# Yaesu_to_CIV_FET.net
KiCad netlist of a schematic drawn in EAGLE
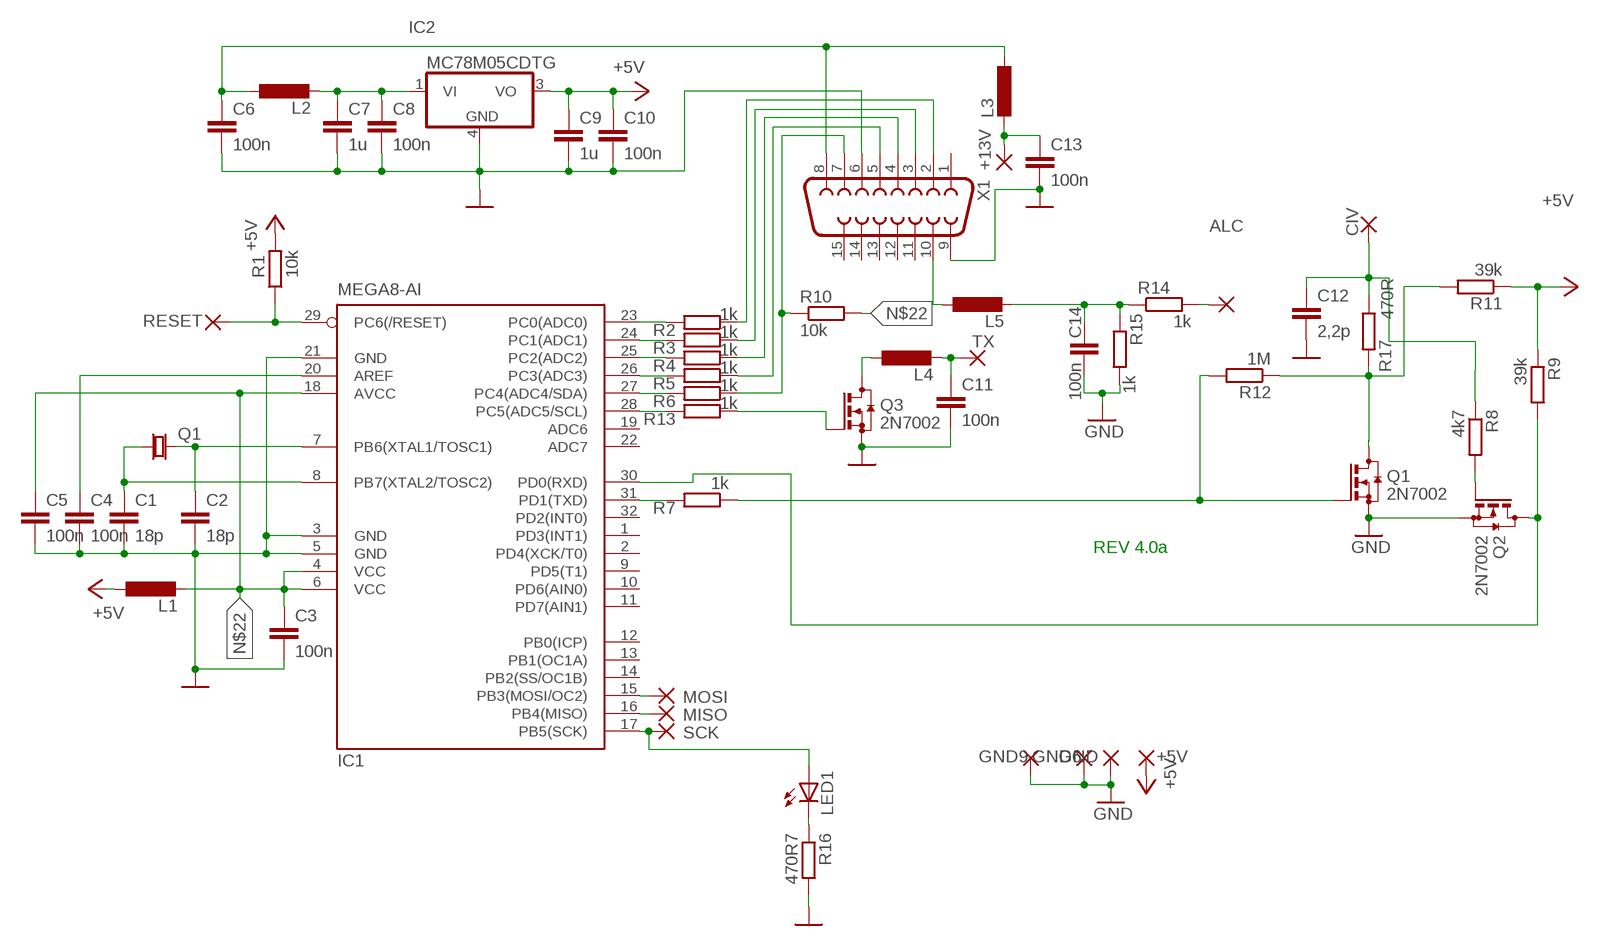
[diagram p0: schematic, sheet 1]

(export (version "E")
  (design (tool "Eeschema 10.0.6"))
  (components
    (comp (ref "+5V")
      (value "SMD2")
      (footprint "eagle-import:SMD1,27-2,54")
      (libsource (lib "eagle-import") (part "SMD2"))
    )
    (comp (ref "+13V")
      (value "SMD2")
      (footprint "eagle-import:SMD1,27-2,54")
      (libsource (lib "eagle-import") (part "SMD2"))
    )
    (comp (ref "ALC")
      (value "SMD2")
      (footprint "eagle-import:SMD1,27-2,54")
      (libsource (lib "eagle-import") (part "SMD2"))
    )
    (comp (ref "C1")
      (value "18p")
      (footprint "eagle-import:C0603K")
      (libsource (lib "eagle-import") (part "C-EUC0603K"))
    )
    (comp (ref "C2")
      (value "18p")
      (footprint "eagle-import:C0603K")
      (libsource (lib "eagle-import") (part "C-EUC0603K"))
    )
    (comp (ref "C3")
      (value "100n")
      (footprint "eagle-import:C0603K")
      (libsource (lib "eagle-import") (part "C-EUC0603K"))
    )
    (comp (ref "C4")
      (value "100n")
      (footprint "eagle-import:C0603K")
      (libsource (lib "eagle-import") (part "C-EUC0603K"))
    )
    (comp (ref "C5")
      (value "100n")
      (footprint "eagle-import:C0603K")
      (libsource (lib "eagle-import") (part "C-EUC0603K"))
    )
    (comp (ref "C6")
      (value "100n")
      (footprint "eagle-import:C0603K")
      (libsource (lib "eagle-import") (part "C-EUC0603K"))
    )
    (comp (ref "C7")
      (value "1u")
      (footprint "eagle-import:C0805K")
      (libsource (lib "eagle-import") (part "C-EUC0805K"))
    )
    (comp (ref "C8")
      (value "100n")
      (footprint "eagle-import:C0603K")
      (libsource (lib "eagle-import") (part "C-EUC0603K"))
    )
    (comp (ref "C9")
      (value "1u")
      (footprint "eagle-import:C0805K")
      (libsource (lib "eagle-import") (part "C-EUC0805K"))
    )
    (comp (ref "C10")
      (value "100n")
      (footprint "eagle-import:C0603K")
      (libsource (lib "eagle-import") (part "C-EUC0603K"))
    )
    (comp (ref "C11")
      (value "100n")
      (footprint "eagle-import:C0603K")
      (libsource (lib "eagle-import") (part "C-EUC0603K"))
    )
    (comp (ref "C12")
      (value "2,2p")
      (footprint "eagle-import:C0603K")
      (libsource (lib "eagle-import") (part "C-EUC0603K"))
    )
    (comp (ref "C13")
      (value "100n")
      (footprint "eagle-import:C0603K")
      (libsource (lib "eagle-import") (part "C-EUC0603K"))
    )
    (comp (ref "C14")
      (value "100n")
      (footprint "eagle-import:C0603K")
      (libsource (lib "eagle-import") (part "C-EUC0603K"))
    )
    (comp (ref "CIV")
      (value "SMD2")
      (footprint "eagle-import:SMD1,27-2,54")
      (libsource (lib "eagle-import") (part "SMD2"))
    )
    (comp (ref "GND")
      (value "SMD2")
      (footprint "eagle-import:SMD1,27-2,54")
      (libsource (lib "eagle-import") (part "SMD2"))
    )
    (comp (ref "GND6")
      (value "SMD2")
      (footprint "eagle-import:SMD1,27-2,54")
      (libsource (lib "eagle-import") (part "SMD2"))
    )
    (comp (ref "GND9")
      (value "SMD2")
      (footprint "eagle-import:SMD1,27-2,54")
      (libsource (lib "eagle-import") (part "SMD2"))
    )
    (comp (ref "IC1")
      (value "MEGA8-AI")
      (footprint "eagle-import:TQFP32-08")
      (fields (field (name "MPN") "ATMEGA8-16AU"))
      (libsource (lib "eagle-import") (part "MEGA8-AI"))
    )
    (comp (ref "IC2")
      (value "MC78M05CDTG")
      (footprint "eagle-import:DPACK_3")
      (libsource (lib "eagle-import") (part "MC78M05CDTG"))
    )
    (comp (ref "L1")
      (value "L-EUL2012C")
      (footprint "eagle-import:L2012C")
      (libsource (lib "eagle-import") (part "L-EUL2012C"))
    )
    (comp (ref "L2")
      (value "L-EUL1812")
      (footprint "eagle-import:L1812")
      (libsource (lib "eagle-import") (part "L-EUL1812"))
    )
    (comp (ref "L3")
      (value "L-EUL1812")
      (footprint "eagle-import:L1812")
      (libsource (lib "eagle-import") (part "L-EUL1812"))
    )
    (comp (ref "L4")
      (value "L-EUL2012C")
      (footprint "eagle-import:L2012C")
      (libsource (lib "eagle-import") (part "L-EUL2012C"))
    )
    (comp (ref "L5")
      (value "L-EUL2012C")
      (footprint "eagle-import:L2012C")
      (libsource (lib "eagle-import") (part "L-EUL2012C"))
    )
    (comp (ref "LED1")
      (value "LEDCHIP-LED0603")
      (footprint "eagle-import:CHIP-LED0603")
      (libsource (lib "eagle-import") (part "LEDCHIP-LED0603"))
    )
    (comp (ref "MISO")
      (value "SMD2")
      (footprint "eagle-import:SMD1,27-2,54")
      (libsource (lib "eagle-import") (part "SMD2"))
    )
    (comp (ref "MOSI")
      (value "SMD2")
      (footprint "eagle-import:SMD1,27-2,54")
      (libsource (lib "eagle-import") (part "SMD2"))
    )
    (comp (ref "Q1")
      (value "2N7002")
      (footprint "eagle-import:SOT23")
      (libsource (lib "eagle-import") (part "BSS123"))
    )
    (comp (ref "Q2")
      (value "2N7002")
      (footprint "eagle-import:SOT23")
      (libsource (lib "eagle-import") (part "BSS123"))
    )
    (comp (ref "Q3")
      (value "2N7002")
      (footprint "eagle-import:SOT23")
      (libsource (lib "eagle-import") (part "BSS123"))
    )
    (comp (ref "R1")
      (value "10k")
      (footprint "eagle-import:R0603")
      (libsource (lib "eagle-import") (part "R-EU_R0603"))
    )
    (comp (ref "R2")
      (value "1k")
      (footprint "eagle-import:R0603")
      (libsource (lib "eagle-import") (part "R-EU_R0603"))
    )
    (comp (ref "R3")
      (value "1k")
      (footprint "eagle-import:R0603")
      (libsource (lib "eagle-import") (part "R-EU_R0603"))
    )
    (comp (ref "R4")
      (value "1k")
      (footprint "eagle-import:R0603")
      (libsource (lib "eagle-import") (part "R-EU_R0603"))
    )
    (comp (ref "R5")
      (value "1k")
      (footprint "eagle-import:R0603")
      (libsource (lib "eagle-import") (part "R-EU_R0603"))
    )
    (comp (ref "R6")
      (value "1k")
      (footprint "eagle-import:R0603")
      (libsource (lib "eagle-import") (part "R-EU_R0603"))
    )
    (comp (ref "R7")
      (value "1k")
      (footprint "eagle-import:R0603")
      (libsource (lib "eagle-import") (part "R-EU_R0603"))
    )
    (comp (ref "R8")
      (value "4k7")
      (footprint "eagle-import:R0603")
      (libsource (lib "eagle-import") (part "R-EU_R0603"))
    )
    (comp (ref "R9")
      (value "39k")
      (footprint "eagle-import:R0603")
      (libsource (lib "eagle-import") (part "R-EU_R0603"))
    )
    (comp (ref "R10")
      (value "10k")
      (footprint "eagle-import:R0603")
      (libsource (lib "eagle-import") (part "R-EU_R0603"))
    )
    (comp (ref "R11")
      (value "39k")
      (footprint "eagle-import:R0603")
      (libsource (lib "eagle-import") (part "R-EU_R0603"))
    )
    (comp (ref "R12")
      (value "1M")
      (footprint "eagle-import:R0603")
      (libsource (lib "eagle-import") (part "R-EU_R0603"))
    )
    (comp (ref "R13")
      (value "1k")
      (footprint "eagle-import:R0603")
      (libsource (lib "eagle-import") (part "R-EU_R0603"))
    )
    (comp (ref "R14")
      (value "1k")
      (footprint "eagle-import:R0603")
      (libsource (lib "eagle-import") (part "R-EU_R0603"))
    )
    (comp (ref "R15")
      (value "1k")
      (footprint "eagle-import:R0603")
      (libsource (lib "eagle-import") (part "R-EU_R0603"))
    )
    (comp (ref "R16")
      (value "470R7")
      (footprint "eagle-import:R0603")
      (libsource (lib "eagle-import") (part "R-EU_R0603"))
    )
    (comp (ref "R17")
      (value "470R")
      (footprint "eagle-import:R0603")
      (libsource (lib "eagle-import") (part "R-EU_R0603"))
    )
    (comp (ref "RESET")
      (value "SMD2")
      (footprint "eagle-import:SMD1,27-2,54")
      (libsource (lib "eagle-import") (part "SMD2"))
    )
    (comp (ref "SCK")
      (value "SMD2")
      (footprint "eagle-import:SMD1,27-2,54")
      (libsource (lib "eagle-import") (part "SMD2"))
    )
    (comp (ref "TX")
      (value "SMD2")
      (footprint "eagle-import:SMD1,27-2,54")
      (libsource (lib "eagle-import") (part "SMD2"))
    )
    (comp (ref "X1")
      (value "F15D")
      (footprint "eagle-import:F15D")
      (libsource (lib "eagle-import") (part "F15D"))
    )
  )
  (nets
    (net (code "1") (name "+5V") (class "Default")
      (node (ref "+5V") (pin "1") (pinfunction "P_1") (pintype "passive"))
      (node (ref "C10") (pin "1") (pinfunction "1_1") (pintype "passive"))
      (node (ref "C9") (pin "1") (pinfunction "1_1") (pintype "passive"))
      (node (ref "IC2") (pin "3") (pinfunction "VO_3") (pintype "passive"))
      (node (ref "L1") (pin "1") (pinfunction "1_1") (pintype "passive"))
      (node (ref "R1") (pin "2") (pinfunction "2_2") (pintype "passive"))
      (node (ref "R11") (pin "1") (pinfunction "1_1") (pintype "passive"))
      (node (ref "R9") (pin "1") (pinfunction "1_1") (pintype "passive"))
    )
    (net (code "2") (name "GND") (class "Default")
      (node (ref "C1") (pin "2") (pinfunction "2_2") (pintype "passive"))
      (node (ref "C10") (pin "2") (pinfunction "2_2") (pintype "passive"))
      (node (ref "C11") (pin "2") (pinfunction "2_2") (pintype "passive"))
      (node (ref "C12") (pin "2") (pinfunction "2_2") (pintype "passive"))
      (node (ref "C13") (pin "2") (pinfunction "2_2") (pintype "passive"))
      (node (ref "C14") (pin "2") (pinfunction "2_2") (pintype "passive"))
      (node (ref "C2") (pin "2") (pinfunction "2_2") (pintype "passive"))
      (node (ref "C3") (pin "2") (pinfunction "2_2") (pintype "passive"))
      (node (ref "C4") (pin "2") (pinfunction "2_2") (pintype "passive"))
      (node (ref "C5") (pin "2") (pinfunction "2_2") (pintype "passive"))
      (node (ref "C6") (pin "2") (pinfunction "2_2") (pintype "passive"))
      (node (ref "C7") (pin "2") (pinfunction "2_2") (pintype "passive"))
      (node (ref "C8") (pin "2") (pinfunction "2_2") (pintype "passive"))
      (node (ref "C9") (pin "2") (pinfunction "2_2") (pintype "passive"))
      (node (ref "GND") (pin "1") (pinfunction "P_1") (pintype "passive"))
      (node (ref "GND6") (pin "1") (pinfunction "P_1") (pintype "passive"))
      (node (ref "GND9") (pin "1") (pinfunction "P_1") (pintype "passive"))
      (node (ref "IC1") (pin "21") (pinfunction "GND_21") (pintype "power_in"))
      (node (ref "IC1") (pin "3") (pinfunction "GND_3") (pintype "power_in"))
      (node (ref "IC1") (pin "5") (pinfunction "GND_5") (pintype "power_in"))
      (node (ref "IC2") (pin "4") (pinfunction "GND_4") (pintype "passive"))
      (node (ref "Q1") (pin "2") (pinfunction "S_2") (pintype "passive"))
      (node (ref "Q2") (pin "2") (pinfunction "S_2") (pintype "passive"))
      (node (ref "Q3") (pin "2") (pinfunction "S_2") (pintype "passive"))
      (node (ref "R15") (pin "2") (pinfunction "2_2") (pintype "passive"))
      (node (ref "R16") (pin "2") (pinfunction "2_2") (pintype "passive"))
      (node (ref "X1") (pin "6") (pinfunction "6_6") (pintype "passive"))
      (node (ref "X1") (pin "9") (pinfunction "9_9") (pintype "passive"))
    )
    (net (code "3") (name "N$22") (class "Default")
      (node (ref "C3") (pin "1") (pinfunction "1_1") (pintype "passive"))
      (node (ref "C5") (pin "1") (pinfunction "1_1") (pintype "passive"))
      (node (ref "IC1") (pin "18") (pinfunction "AVCC_18") (pintype "power_in"))
      (node (ref "IC1") (pin "4") (pinfunction "VCC_4") (pintype "power_in"))
      (node (ref "IC1") (pin "6") (pinfunction "VCC_6") (pintype "power_in"))
      (node (ref "L1") (pin "2") (pinfunction "2_2") (pintype "passive"))
      (node (ref "R10") (pin "2") (pinfunction "2_2") (pintype "passive"))
    )
    (net (code "4") (name "Net-(+13V-P)") (class "Default")
      (node (ref "+13V") (pin "1") (pinfunction "P_1") (pintype "passive"))
      (node (ref "C13") (pin "1") (pinfunction "1_1") (pintype "passive"))
      (node (ref "L3") (pin "2") (pinfunction "2_2") (pintype "passive"))
    )
    (net (code "5") (name "Net-(ALC-P)") (class "Default")
      (node (ref "ALC") (pin "1") (pinfunction "P_1") (pintype "passive"))
      (node (ref "R14") (pin "2") (pinfunction "2_2") (pintype "passive"))
    )
    (net (code "6") (name "Net-(C6-Pad1)") (class "Default")
      (node (ref "C6") (pin "1") (pinfunction "1_1") (pintype "passive"))
      (node (ref "L2") (pin "1") (pinfunction "1_1") (pintype "passive"))
      (node (ref "L3") (pin "1") (pinfunction "1_1") (pintype "passive"))
      (node (ref "X1") (pin "8") (pinfunction "8_8") (pintype "passive"))
    )
    (net (code "7") (name "Net-(C14-Pad1)") (class "Default")
      (node (ref "C14") (pin "1") (pinfunction "1_1") (pintype "passive"))
      (node (ref "L5") (pin "2") (pinfunction "2_2") (pintype "passive"))
      (node (ref "R14") (pin "1") (pinfunction "1_1") (pintype "passive"))
      (node (ref "R15") (pin "1") (pinfunction "1_1") (pintype "passive"))
    )
    (net (code "8") (name "Net-(CIV-P)") (class "Default")
      (node (ref "C12") (pin "1") (pinfunction "1_1") (pintype "passive"))
      (node (ref "CIV") (pin "1") (pinfunction "P_1") (pintype "passive"))
      (node (ref "R17") (pin "1") (pinfunction "1_1") (pintype "passive"))
      (node (ref "R8") (pin "1") (pinfunction "1_1") (pintype "passive"))
    )
    (net (code "9") (name "Net-(IC1-AREF)") (class "Default")
      (node (ref "C4") (pin "1") (pinfunction "1_1") (pintype "passive"))
      (node (ref "IC1") (pin "20") (pinfunction "AREF_20") (pintype "passive"))
    )
    (net (code "10") (name "Net-(IC1-PB3(MOSI{slash}OC2))") (class "Default")
      (node (ref "IC1") (pin "15") (pinfunction "PB3(MOSI/OC2)_15") (pintype "bidirectional"))
      (node (ref "MOSI") (pin "1") (pinfunction "P_1") (pintype "passive"))
    )
    (net (code "11") (name "Net-(IC1-PB4(MISO))") (class "Default")
      (node (ref "IC1") (pin "16") (pinfunction "PB4(MISO)_16") (pintype "bidirectional"))
      (node (ref "MISO") (pin "1") (pinfunction "P_1") (pintype "passive"))
    )
    (net (code "12") (name "Net-(IC1-PB5(SCK))") (class "Default")
      (node (ref "IC1") (pin "17") (pinfunction "PB5(SCK)_17") (pintype "bidirectional"))
      (node (ref "LED1") (pin "A") (pinfunction "A_A") (pintype "passive"))
      (node (ref "SCK") (pin "1") (pinfunction "P_1") (pintype "passive"))
    )
    (net (code "13") (name "Net-(IC1-PB6(XTAL1{slash}TOSC1))") (class "Default")
      (node (ref "C2") (pin "1") (pinfunction "1_1") (pintype "passive"))
      (node (ref "IC1") (pin "7") (pinfunction "PB6(XTAL1/TOSC1)_7") (pintype "bidirectional"))
    )
    (net (code "14") (name "Net-(IC1-PB7(XTAL2{slash}TOSC2))") (class "Default")
      (node (ref "C1") (pin "1") (pinfunction "1_1") (pintype "passive"))
      (node (ref "IC1") (pin "8") (pinfunction "PB7(XTAL2/TOSC2)_8") (pintype "bidirectional"))
    )
    (net (code "15") (name "Net-(IC1-PC0(ADC0))") (class "Default")
      (node (ref "IC1") (pin "23") (pinfunction "PC0(ADC0)_23") (pintype "bidirectional"))
      (node (ref "R2") (pin "2") (pinfunction "2_2") (pintype "passive"))
    )
    (net (code "16") (name "Net-(IC1-PC1(ADC1))") (class "Default")
      (node (ref "IC1") (pin "24") (pinfunction "PC1(ADC1)_24") (pintype "bidirectional"))
      (node (ref "R3") (pin "2") (pinfunction "2_2") (pintype "passive"))
    )
    (net (code "17") (name "Net-(IC1-PC2(ADC2))") (class "Default")
      (node (ref "IC1") (pin "25") (pinfunction "PC2(ADC2)_25") (pintype "bidirectional"))
      (node (ref "R4") (pin "2") (pinfunction "2_2") (pintype "passive"))
    )
    (net (code "18") (name "Net-(IC1-PC3(ADC3))") (class "Default")
      (node (ref "IC1") (pin "26") (pinfunction "PC3(ADC3)_26") (pintype "bidirectional"))
      (node (ref "R5") (pin "2") (pinfunction "2_2") (pintype "passive"))
    )
    (net (code "19") (name "Net-(IC1-PC4(ADC4{slash}SDA))") (class "Default")
      (node (ref "IC1") (pin "27") (pinfunction "PC4(ADC4/SDA)_27") (pintype "bidirectional"))
      (node (ref "R6") (pin "2") (pinfunction "2_2") (pintype "passive"))
    )
    (net (code "20") (name "Net-(IC1-PC5(ADC5{slash}SCL))") (class "Default")
      (node (ref "IC1") (pin "28") (pinfunction "PC5(ADC5/SCL)_28") (pintype "bidirectional"))
      (node (ref "R13") (pin "2") (pinfunction "2_2") (pintype "passive"))
    )
    (net (code "21") (name "Net-(IC1-PC6({slash}RESET))") (class "Default")
      (node (ref "IC1") (pin "29") (pinfunction "PC6(/RESET)_29") (pintype "bidirectional"))
      (node (ref "R1") (pin "1") (pinfunction "1_1") (pintype "passive"))
      (node (ref "RESET") (pin "1") (pinfunction "P_1") (pintype "passive"))
    )
    (net (code "22") (name "Net-(IC1-PD0(RXD))") (class "Default")
      (node (ref "IC1") (pin "30") (pinfunction "PD0(RXD)_30") (pintype "bidirectional"))
      (node (ref "Q2") (pin "3") (pinfunction "D_3") (pintype "passive"))
      (node (ref "R9") (pin "2") (pinfunction "2_2") (pintype "passive"))
    )
    (net (code "23") (name "Net-(IC1-PD1(TXD))") (class "Default")
      (node (ref "IC1") (pin "31") (pinfunction "PD1(TXD)_31") (pintype "bidirectional"))
      (node (ref "R7") (pin "2") (pinfunction "2_2") (pintype "passive"))
    )
    (net (code "24") (name "Net-(IC2-VI)") (class "Default")
      (node (ref "C7") (pin "1") (pinfunction "1_1") (pintype "passive"))
      (node (ref "C8") (pin "1") (pinfunction "1_1") (pintype "passive"))
      (node (ref "IC2") (pin "1") (pinfunction "VI_1") (pintype "input"))
      (node (ref "L2") (pin "2") (pinfunction "2_2") (pintype "passive"))
    )
    (net (code "25") (name "Net-(L5-Pad1)") (class "Default")
      (node (ref "L5") (pin "1") (pinfunction "1_1") (pintype "passive"))
      (node (ref "X1") (pin "10") (pinfunction "10_10") (pintype "passive"))
    )
    (net (code "26") (name "Net-(LED1-PadC)") (class "Default")
      (node (ref "LED1") (pin "C") (pinfunction "C_C") (pintype "passive"))
      (node (ref "R16") (pin "1") (pinfunction "1_1") (pintype "passive"))
    )
    (net (code "27") (name "Net-(Q1-G)") (class "Default")
      (node (ref "Q1") (pin "1") (pinfunction "G_1") (pintype "passive"))
      (node (ref "R12") (pin "2") (pinfunction "2_2") (pintype "passive"))
      (node (ref "R7") (pin "1") (pinfunction "1_1") (pintype "passive"))
    )
    (net (code "28") (name "Net-(Q2-G)") (class "Default")
      (node (ref "Q2") (pin "1") (pinfunction "G_1") (pintype "passive"))
      (node (ref "R8") (pin "2") (pinfunction "2_2") (pintype "passive"))
    )
    (net (code "29") (name "Net-(Q3-D)") (class "Default")
      (node (ref "L4") (pin "1") (pinfunction "1_1") (pintype "passive"))
      (node (ref "Q3") (pin "3") (pinfunction "D_3") (pintype "passive"))
    )
    (net (code "30") (name "Net-(Q3-G)") (class "Default")
      (node (ref "Q3") (pin "1") (pinfunction "G_1") (pintype "passive"))
      (node (ref "R13") (pin "1") (pinfunction "1_1") (pintype "passive"))
    )
    (net (code "31") (name "Net-(R2-Pad1)") (class "Default")
      (node (ref "R2") (pin "1") (pinfunction "1_1") (pintype "passive"))
      (node (ref "X1") (pin "2") (pinfunction "2_2") (pintype "passive"))
    )
    (net (code "32") (name "Net-(R3-Pad1)") (class "Default")
      (node (ref "R3") (pin "1") (pinfunction "1_1") (pintype "passive"))
      (node (ref "X1") (pin "3") (pinfunction "3_3") (pintype "passive"))
    )
    (net (code "33") (name "Net-(R4-Pad1)") (class "Default")
      (node (ref "R4") (pin "1") (pinfunction "1_1") (pintype "passive"))
      (node (ref "X1") (pin "4") (pinfunction "4_4") (pintype "passive"))
    )
    (net (code "34") (name "Net-(R5-Pad1)") (class "Default")
      (node (ref "R5") (pin "1") (pinfunction "1_1") (pintype "passive"))
      (node (ref "X1") (pin "5") (pinfunction "5_5") (pintype "passive"))
    )
    (net (code "35") (name "Net-(R10-Pad1)") (class "Default")
      (node (ref "R10") (pin "1") (pinfunction "1_1") (pintype "passive"))
      (node (ref "R6") (pin "1") (pinfunction "1_1") (pintype "passive"))
      (node (ref "X1") (pin "7") (pinfunction "7_7") (pintype "passive"))
    )
    (net (code "36") (name "Net-(R11-Pad2)") (class "Default")
      (node (ref "R11") (pin "2") (pinfunction "2_2") (pintype "passive"))
      (node (ref "R12") (pin "1") (pinfunction "1_1") (pintype "passive"))
      (node (ref "R17") (pin "2") (pinfunction "2_2") (pintype "passive"))
    )
    (net (code "37") (name "Net-(TX-P)") (class "Default")
      (node (ref "C11") (pin "1") (pinfunction "1_1") (pintype "passive"))
      (node (ref "L4") (pin "2") (pinfunction "2_2") (pintype "passive"))
      (node (ref "TX") (pin "1") (pinfunction "P_1") (pintype "passive"))
    )
    (net (code "38") (name "unconnected-(IC1-ADC6-Pad19)") (class "Default")
      (node (ref "IC1") (pin "19") (pinfunction "ADC6_19") (pintype "bidirectional"))
    )
    (net (code "39") (name "unconnected-(IC1-ADC7-Pad22)") (class "Default")
      (node (ref "IC1") (pin "22") (pinfunction "ADC7_22") (pintype "bidirectional"))
    )
    (net (code "40") (name "unconnected-(IC1-PB0(ICP)-Pad12)") (class "Default")
      (node (ref "IC1") (pin "12") (pinfunction "PB0(ICP)_12") (pintype "bidirectional"))
    )
    (net (code "41") (name "unconnected-(IC1-PB1(OC1A)-Pad13)") (class "Default")
      (node (ref "IC1") (pin "13") (pinfunction "PB1(OC1A)_13") (pintype "bidirectional"))
    )
    (net (code "42") (name "unconnected-(IC1-PB2(SS{slash}OC1B)-Pad14)") (class "Default")
      (node (ref "IC1") (pin "14") (pinfunction "PB2(SS/OC1B)_14") (pintype "bidirectional"))
    )
    (net (code "43") (name "unconnected-(IC1-PD2(INT0)-Pad32)") (class "Default")
      (node (ref "IC1") (pin "32") (pinfunction "PD2(INT0)_32") (pintype "bidirectional"))
    )
    (net (code "44") (name "unconnected-(IC1-PD3(INT1)-Pad1)") (class "Default")
      (node (ref "IC1") (pin "1") (pinfunction "PD3(INT1)_1") (pintype "bidirectional"))
    )
    (net (code "45") (name "unconnected-(IC1-PD4(XCK{slash}T0)-Pad2)") (class "Default")
      (node (ref "IC1") (pin "2") (pinfunction "PD4(XCK/T0)_2") (pintype "bidirectional"))
    )
    (net (code "46") (name "unconnected-(IC1-PD5(T1)-Pad9)") (class "Default")
      (node (ref "IC1") (pin "9") (pinfunction "PD5(T1)_9") (pintype "bidirectional"))
    )
    (net (code "47") (name "unconnected-(IC1-PD6(AIN0)-Pad10)") (class "Default")
      (node (ref "IC1") (pin "10") (pinfunction "PD6(AIN0)_10") (pintype "bidirectional"))
    )
    (net (code "48") (name "unconnected-(IC1-PD7(AIN1)-Pad11)") (class "Default")
      (node (ref "IC1") (pin "11") (pinfunction "PD7(AIN1)_11") (pintype "bidirectional"))
    )
    (net (code "49") (name "unconnected-(Q1-D-Pad3)") (class "Default")
      (node (ref "Q1") (pin "3") (pinfunction "D_3") (pintype "passive"))
    )
    (net (code "50") (name "unconnected-(X1-Pad1)") (class "Default")
      (node (ref "X1") (pin "1") (pinfunction "1_1") (pintype "passive"))
    )
    (net (code "51") (name "unconnected-(X1-Pad11)") (class "Default")
      (node (ref "X1") (pin "11") (pinfunction "11_11") (pintype "passive"))
    )
    (net (code "52") (name "unconnected-(X1-Pad12)") (class "Default")
      (node (ref "X1") (pin "12") (pinfunction "12_12") (pintype "passive"))
    )
    (net (code "53") (name "unconnected-(X1-Pad13)") (class "Default")
      (node (ref "X1") (pin "13") (pinfunction "13_13") (pintype "passive"))
    )
    (net (code "54") (name "unconnected-(X1-Pad14)") (class "Default")
      (node (ref "X1") (pin "14") (pinfunction "14_14") (pintype "passive"))
    )
    (net (code "55") (name "unconnected-(X1-Pad15)") (class "Default")
      (node (ref "X1") (pin "15") (pinfunction "15_15") (pintype "passive"))
    )
  )
)
